# Sch.net
KiCad netlist of a schematic drawn in Altium Designer
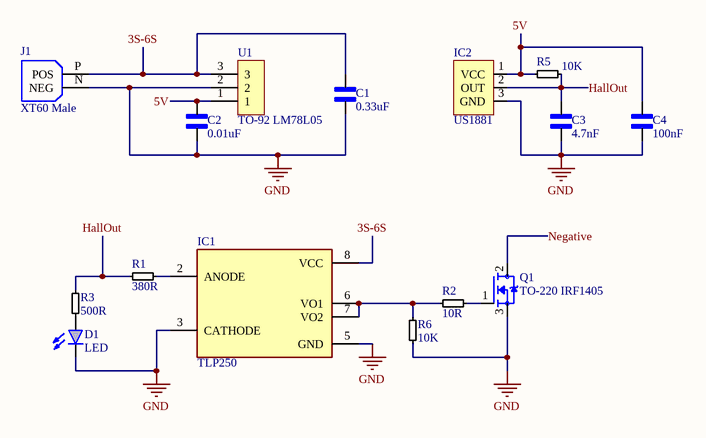
[diagram p0: Sch.SchDoc]

(export (version "E")
  (design (tool "Eeschema 10.0.6"))
  (components
    (comp (ref "C1")
      (value "0.33uF")
      (footprint "CER-DIP-CAP")
      (libsource (lib "MYS-Library") (part "CAP DIP"))
    )
    (comp (ref "C2")
      (value "0.01uF")
      (footprint "CER-DIP-CAP")
      (libsource (lib "MYS-Library") (part "CAP DIP"))
    )
    (comp (ref "C3")
      (value "4.7nF")
      (footprint "CER-DIP-CAP")
      (libsource (lib "MYS-Library") (part "CAP DIP"))
    )
    (comp (ref "C4")
      (value "100nF")
      (footprint "CER-DIP-CAP")
      (libsource (lib "MYS-Library") (part "CAP DIP"))
    )
    (comp (ref "D1") (value "LED") (footprint "LED DIP") (libsource (lib "MYS-Library") (part "LED DIP")))
    (comp (ref "IC1")
      (value "TLP250")
      (footprint "DIP-8")
      (libsource (lib "MYS-Library") (part "TLP250-DIP"))
    )
    (comp (ref "IC2") (value "US1881") (footprint "UA") (libsource (lib "MYS-Library") (part "US1881")))
    (comp (ref "J1")
      (value "XT60 Male")
      (footprint "XT60 Male Pin")
      (libsource (lib "MYS-Library") (part "XT60 Male Pin"))
    )
    (comp (ref "Q1")
      (value "TO-220 IRF1405")
      (footprint "TO-220")
      (libsource (lib "MYS-Library") (part "TO-220 MOSFET"))
    )
    (comp (ref "R1") (value "380R") (footprint "RES DIP") (libsource (lib "MYS-Library") (part "RES DIP")))
    (comp (ref "R2") (value "10R") (footprint "RES DIP") (libsource (lib "MYS-Library") (part "RES DIP")))
    (comp (ref "R3") (value "500R") (footprint "RES DIP") (libsource (lib "MYS-Library") (part "RES DIP")))
    (comp (ref "R5") (value "10K") (footprint "RES DIP") (libsource (lib "MYS-Library") (part "RES DIP")))
    (comp (ref "R6") (value "10K") (footprint "RES DIP") (libsource (lib "MYS-Library") (part "RES DIP")))
    (comp (ref "U1")
      (value "TO-92 LM78L05")
      (footprint "TO-226 TO-92")
      (libsource (lib "MYS-Library") (part "TO-92"))
    )
  )
  (nets
    (net (code "1") (name "/3S-6S") (class "Default")
      (node (ref "C1") (pin "2") (pinfunction "2_2") (pintype "passive"))
      (node (ref "IC1") (pin "8") (pinfunction "VCC_8") (pintype "power_in"))
      (node (ref "J1") (pin "P") (pinfunction "POS_P") (pintype "passive"))
      (node (ref "U1") (pin "3") (pinfunction "3_3") (pintype "passive"))
    )
    (net (code "2") (name "/5V") (class "Default")
      (node (ref "C2") (pin "2") (pinfunction "2_2") (pintype "passive"))
      (node (ref "C4") (pin "2") (pinfunction "2_2") (pintype "passive"))
      (node (ref "IC2") (pin "1") (pinfunction "VCC_1") (pintype "passive"))
      (node (ref "R5") (pin "1") (pinfunction "1_1") (pintype "passive"))
      (node (ref "U1") (pin "1") (pinfunction "1_1") (pintype "passive"))
    )
    (net (code "3") (name "/HallOut") (class "Default")
      (node (ref "C3") (pin "2") (pinfunction "2_2") (pintype "passive"))
      (node (ref "IC2") (pin "2") (pinfunction "OUT_2") (pintype "passive"))
      (node (ref "R1") (pin "1") (pinfunction "1_1") (pintype "passive"))
      (node (ref "R3") (pin "1") (pinfunction "1_1") (pintype "passive"))
      (node (ref "R5") (pin "2") (pinfunction "2_2") (pintype "passive"))
    )
    (net (code "4") (name "/Negative") (class "Default")
      (node (ref "Q1") (pin "2") (pinfunction "D_2") (pintype "passive"))
    )
    (net (code "5") (name "GND") (class "Default")
      (node (ref "C1") (pin "1") (pinfunction "1_1") (pintype "passive"))
      (node (ref "C2") (pin "1") (pinfunction "1_1") (pintype "passive"))
      (node (ref "C3") (pin "1") (pinfunction "1_1") (pintype "passive"))
      (node (ref "C4") (pin "1") (pinfunction "1_1") (pintype "passive"))
      (node (ref "D1") (pin "C") (pinfunction "C_C") (pintype "passive"))
      (node (ref "IC1") (pin "3") (pinfunction "CATHODE_3") (pintype "passive"))
      (node (ref "IC1") (pin "5") (pinfunction "GND_5") (pintype "power_in"))
      (node (ref "IC2") (pin "3") (pinfunction "GND_3") (pintype "passive"))
      (node (ref "J1") (pin "N") (pinfunction "NEG_N") (pintype "passive"))
      (node (ref "Q1") (pin "3") (pinfunction "S_3") (pintype "passive"))
      (node (ref "R6") (pin "1") (pinfunction "1_1") (pintype "passive"))
      (node (ref "U1") (pin "2") (pinfunction "2_2") (pintype "passive"))
    )
    (net (code "6") (name "Net-(D1-PadA)") (class "Default")
      (node (ref "D1") (pin "A") (pinfunction "A_A") (pintype "passive"))
      (node (ref "R3") (pin "2") (pinfunction "2_2") (pintype "passive"))
    )
    (net (code "7") (name "Net-(IC1-ANODE)") (class "Default")
      (node (ref "IC1") (pin "2") (pinfunction "ANODE_2") (pintype "passive"))
      (node (ref "R1") (pin "2") (pinfunction "2_2") (pintype "passive"))
    )
    (net (code "8") (name "Net-(IC1-VO1)") (class "Default")
      (node (ref "IC1") (pin "6") (pinfunction "VO1_6") (pintype "passive"))
      (node (ref "IC1") (pin "7") (pinfunction "VO2_7") (pintype "passive"))
      (node (ref "R2") (pin "1") (pinfunction "1_1") (pintype "passive"))
      (node (ref "R6") (pin "2") (pinfunction "2_2") (pintype "passive"))
    )
    (net (code "9") (name "Net-(Q1-G)") (class "Default")
      (node (ref "Q1") (pin "1") (pinfunction "G_1") (pintype "passive"))
      (node (ref "R2") (pin "2") (pinfunction "2_2") (pintype "passive"))
    )
  )
)
